# TDA2004.net
KiCad netlist of a schematic drawn in EAGLE
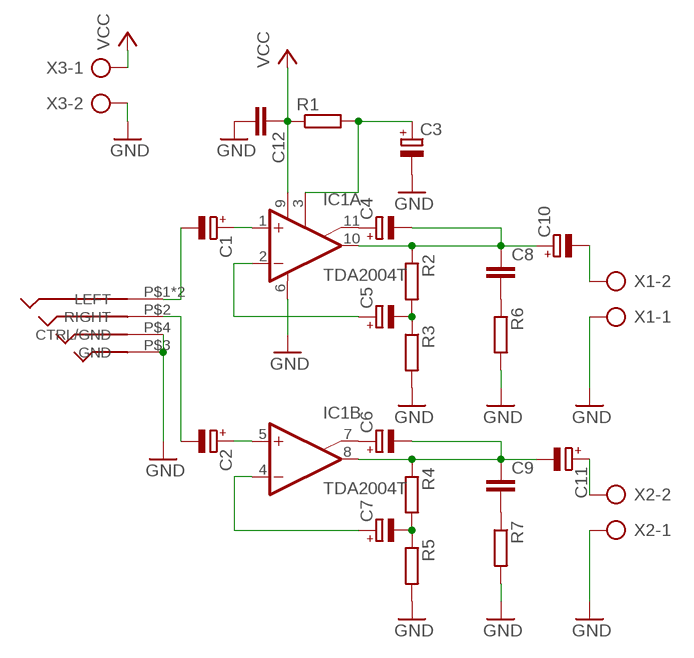
[diagram p0: schematic, sheet 1]

(export (version "E")
  (design (tool "Eeschema 10.0.6"))
  (components
    (comp (ref "C1")
      (value "CPOL-EUE2-5")
      (footprint "eagle-import:E2-5")
      (libsource (lib "eagle-import") (part "CPOL-EUE2-5"))
    )
    (comp (ref "C2")
      (value "CPOL-EUE2-5")
      (footprint "eagle-import:E2-5")
      (libsource (lib "eagle-import") (part "CPOL-EUE2-5"))
    )
    (comp (ref "C3")
      (value "CPOL-EUE2-5")
      (footprint "eagle-import:E2-5")
      (libsource (lib "eagle-import") (part "CPOL-EUE2-5"))
    )
    (comp (ref "C4")
      (value "CPOL-EUE2-5")
      (footprint "eagle-import:E2-5")
      (libsource (lib "eagle-import") (part "CPOL-EUE2-5"))
    )
    (comp (ref "C5")
      (value "CPOL-EUE25-10AXIAL")
      (footprint "eagle-import:E25-10")
      (libsource (lib "eagle-import") (part "CPOL-EUE25-10AXIAL"))
    )
    (comp (ref "C6")
      (value "CPOL-EUE2-5")
      (footprint "eagle-import:E2-5")
      (libsource (lib "eagle-import") (part "CPOL-EUE2-5"))
    )
    (comp (ref "C7")
      (value "CPOL-EUE25-10AXIAL")
      (footprint "eagle-import:E25-10")
      (libsource (lib "eagle-import") (part "CPOL-EUE25-10AXIAL"))
    )
    (comp (ref "C8")
      (value "C-EU050-025X075")
      (footprint "eagle-import:C050-025X075")
      (libsource (lib "eagle-import") (part "C-EU050-025X075"))
    )
    (comp (ref "C9")
      (value "C-EU050-025X075")
      (footprint "eagle-import:C050-025X075")
      (libsource (lib "eagle-import") (part "C-EU050-025X075"))
    )
    (comp (ref "C10")
      (value "CPOL-EUE5-13")
      (footprint "eagle-import:E5-13")
      (libsource (lib "eagle-import") (part "CPOL-EUE5-13"))
    )
    (comp (ref "C11")
      (value "CPOL-EUE5-13")
      (footprint "eagle-import:E5-13")
      (libsource (lib "eagle-import") (part "CPOL-EUE5-13"))
    )
    (comp (ref "C12")
      (value "C-EU050-025X075")
      (footprint "eagle-import:C050-025X075")
      (libsource (lib "eagle-import") (part "C-EU050-025X075"))
    )
    (comp (ref "IC1")
      (value "TDA2004T")
      (footprint "eagle-import:SIP11")
      (libsource (lib "eagle-import") (part "TDA2004T"))
    )
    (comp (ref "R1")
      (value "R-EU_0411/15")
      (footprint "eagle-import:0411_15")
      (libsource (lib "eagle-import") (part "R-EU_0411/15"))
    )
    (comp (ref "R2")
      (value "R-EU_0411/15")
      (footprint "eagle-import:0411_15")
      (libsource (lib "eagle-import") (part "R-EU_0411/15"))
    )
    (comp (ref "R3")
      (value "R-EU_0411/15")
      (footprint "eagle-import:0411_15")
      (libsource (lib "eagle-import") (part "R-EU_0411/15"))
    )
    (comp (ref "R4")
      (value "R-EU_0411/15")
      (footprint "eagle-import:0411_15")
      (libsource (lib "eagle-import") (part "R-EU_0411/15"))
    )
    (comp (ref "R5")
      (value "R-EU_0411/15")
      (footprint "eagle-import:0411_15")
      (libsource (lib "eagle-import") (part "R-EU_0411/15"))
    )
    (comp (ref "R6")
      (value "R-EU_0411/15")
      (footprint "eagle-import:0411_15")
      (libsource (lib "eagle-import") (part "R-EU_0411/15"))
    )
    (comp (ref "R7")
      (value "R-EU_0411/15")
      (footprint "eagle-import:0411_15")
      (libsource (lib "eagle-import") (part "R-EU_0411/15"))
    )
    (comp (ref "U$1")
      (value "3_5MM_JACK")
      (footprint "eagle-import:3_5MM_JACK")
      (libsource (lib "eagle-import") (part "3_5MM_JACK"))
    )
    (comp (ref "X1")
      (value "AK500/2-H")
      (footprint "eagle-import:AK500_2-H")
      (libsource (lib "eagle-import") (part "AK500/2-H"))
    )
    (comp (ref "X2")
      (value "AK500/2-H")
      (footprint "eagle-import:AK500_2-H")
      (libsource (lib "eagle-import") (part "AK500/2-H"))
    )
    (comp (ref "X3")
      (value "AK500/2")
      (footprint "eagle-import:AK500_2")
      (libsource (lib "eagle-import") (part "AK500/2"))
    )
  )
  (nets
    (net (code "1") (name "GND") (class "Default")
      (node (ref "C12") (pin "2") (pinfunction "2_2") (pintype "passive"))
      (node (ref "C3") (pin "-") (pinfunction "-_-") (pintype "passive"))
      (node (ref "IC1") (pin "6") (pinfunction "GND_6") (pintype "power_in"))
      (node (ref "R3") (pin "2") (pinfunction "2_2") (pintype "passive"))
      (node (ref "R5") (pin "2") (pinfunction "2_2") (pintype "passive"))
      (node (ref "R6") (pin "2") (pinfunction "2_2") (pintype "passive"))
      (node (ref "R7") (pin "2") (pinfunction "2_2") (pintype "passive"))
      (node (ref "U$1") (pin "P$3") (pinfunction "GND_P$3") (pintype "bidirectional"))
      (node (ref "U$1") (pin "P$4") (pinfunction "CTRL/GND_P$4") (pintype "bidirectional"))
      (node (ref "X1") (pin "1") (pinfunction "KL_1") (pintype "passive"))
      (node (ref "X2") (pin "1") (pinfunction "KL_1") (pintype "passive"))
      (node (ref "X3") (pin "2") (pinfunction "KL_2") (pintype "passive"))
    )
    (net (code "2") (name "Net-(C1-Pad-)") (class "Default")
      (node (ref "C1") (pin "-") (pinfunction "-_-") (pintype "passive"))
      (node (ref "U$1") (pin "P$1") (pinfunction "LEFT_P$1") (pintype "bidirectional"))
      (node (ref "U$1") (pin "P$5") (pinfunction "LEFT_P$5") (pintype "bidirectional"))
    )
    (net (code "3") (name "Net-(C5-Pad-)") (class "Default")
      (node (ref "C5") (pin "-") (pinfunction "-_-") (pintype "passive"))
      (node (ref "R2") (pin "2") (pinfunction "2_2") (pintype "passive"))
      (node (ref "R3") (pin "1") (pinfunction "1_1") (pintype "passive"))
    )
    (net (code "4") (name "Net-(C7-Pad-)") (class "Default")
      (node (ref "C7") (pin "-") (pinfunction "-_-") (pintype "passive"))
      (node (ref "R4") (pin "2") (pinfunction "2_2") (pintype "passive"))
      (node (ref "R5") (pin "1") (pinfunction "1_1") (pintype "passive"))
    )
    (net (code "5") (name "Net-(C8-Pad2)") (class "Default")
      (node (ref "C8") (pin "2") (pinfunction "2_2") (pintype "passive"))
      (node (ref "R6") (pin "1") (pinfunction "1_1") (pintype "passive"))
    )
    (net (code "6") (name "Net-(C9-Pad2)") (class "Default")
      (node (ref "C9") (pin "2") (pinfunction "2_2") (pintype "passive"))
      (node (ref "R7") (pin "1") (pinfunction "1_1") (pintype "passive"))
    )
    (net (code "7") (name "Net-(IC1A-+IN)") (class "Default")
      (node (ref "C1") (pin "+") (pinfunction "+_+") (pintype "passive"))
      (node (ref "IC1") (pin "1") (pinfunction "+IN_1") (pintype "input"))
    )
    (net (code "8") (name "Net-(IC1A--IN)") (class "Default")
      (node (ref "C5") (pin "+") (pinfunction "+_+") (pintype "passive"))
      (node (ref "IC1") (pin "2") (pinfunction "-IN_2") (pintype "input"))
    )
    (net (code "9") (name "Net-(IC1A-BTSP)") (class "Default")
      (node (ref "C4") (pin "+") (pinfunction "+_+") (pintype "passive"))
      (node (ref "IC1") (pin "11") (pinfunction "BTSP_11") (pintype "passive"))
    )
    (net (code "10") (name "Net-(IC1A-OUT)") (class "Default")
      (node (ref "C10") (pin "+") (pinfunction "+_+") (pintype "passive"))
      (node (ref "C4") (pin "-") (pinfunction "-_-") (pintype "passive"))
      (node (ref "C8") (pin "1") (pinfunction "1_1") (pintype "passive"))
      (node (ref "IC1") (pin "10") (pinfunction "OUT_10") (pintype "output"))
      (node (ref "R2") (pin "1") (pinfunction "1_1") (pintype "passive"))
    )
    (net (code "11") (name "Net-(IC1A-SVRR)") (class "Default")
      (node (ref "C3") (pin "+") (pinfunction "+_+") (pintype "passive"))
      (node (ref "IC1") (pin "3") (pinfunction "SVRR_3") (pintype "passive"))
      (node (ref "R1") (pin "2") (pinfunction "2_2") (pintype "passive"))
    )
    (net (code "12") (name "Net-(IC1B-+IN)") (class "Default")
      (node (ref "C2") (pin "+") (pinfunction "+_+") (pintype "passive"))
      (node (ref "IC1") (pin "5") (pinfunction "+IN_5") (pintype "input"))
    )
    (net (code "13") (name "Net-(IC1B--IN)") (class "Default")
      (node (ref "C7") (pin "+") (pinfunction "+_+") (pintype "passive"))
      (node (ref "IC1") (pin "4") (pinfunction "-IN_4") (pintype "input"))
    )
    (net (code "14") (name "Net-(IC1B-BTSP)") (class "Default")
      (node (ref "C6") (pin "+") (pinfunction "+_+") (pintype "passive"))
      (node (ref "IC1") (pin "7") (pinfunction "BTSP_7") (pintype "passive"))
    )
    (net (code "15") (name "Net-(IC1B-OUT)") (class "Default")
      (node (ref "C11") (pin "-") (pinfunction "-_-") (pintype "passive"))
      (node (ref "C6") (pin "-") (pinfunction "-_-") (pintype "passive"))
      (node (ref "C9") (pin "1") (pinfunction "1_1") (pintype "passive"))
      (node (ref "IC1") (pin "8") (pinfunction "OUT_8") (pintype "output"))
      (node (ref "R4") (pin "1") (pinfunction "1_1") (pintype "passive"))
    )
    (net (code "16") (name "Net-(U$1-RIGHT)") (class "Default")
      (node (ref "C2") (pin "-") (pinfunction "-_-") (pintype "passive"))
      (node (ref "U$1") (pin "P$2") (pinfunction "RIGHT_P$2") (pintype "bidirectional"))
    )
    (net (code "17") (name "Net-(X1B-KL)") (class "Default")
      (node (ref "C10") (pin "-") (pinfunction "-_-") (pintype "passive"))
      (node (ref "X1") (pin "2") (pinfunction "KL_2") (pintype "passive"))
    )
    (net (code "18") (name "Net-(X2B-KL)") (class "Default")
      (node (ref "C11") (pin "+") (pinfunction "+_+") (pintype "passive"))
      (node (ref "X2") (pin "2") (pinfunction "KL_2") (pintype "passive"))
    )
    (net (code "19") (name "VCC") (class "Default")
      (node (ref "C12") (pin "1") (pinfunction "1_1") (pintype "passive"))
      (node (ref "IC1") (pin "9") (pinfunction "V+_9") (pintype "power_in"))
      (node (ref "R1") (pin "1") (pinfunction "1_1") (pintype "passive"))
      (node (ref "X3") (pin "1") (pinfunction "KL_1") (pintype "passive"))
    )
  )
)
